# SOCConfiguration.net
KiCad netlist of a schematic drawn in Altium Designer
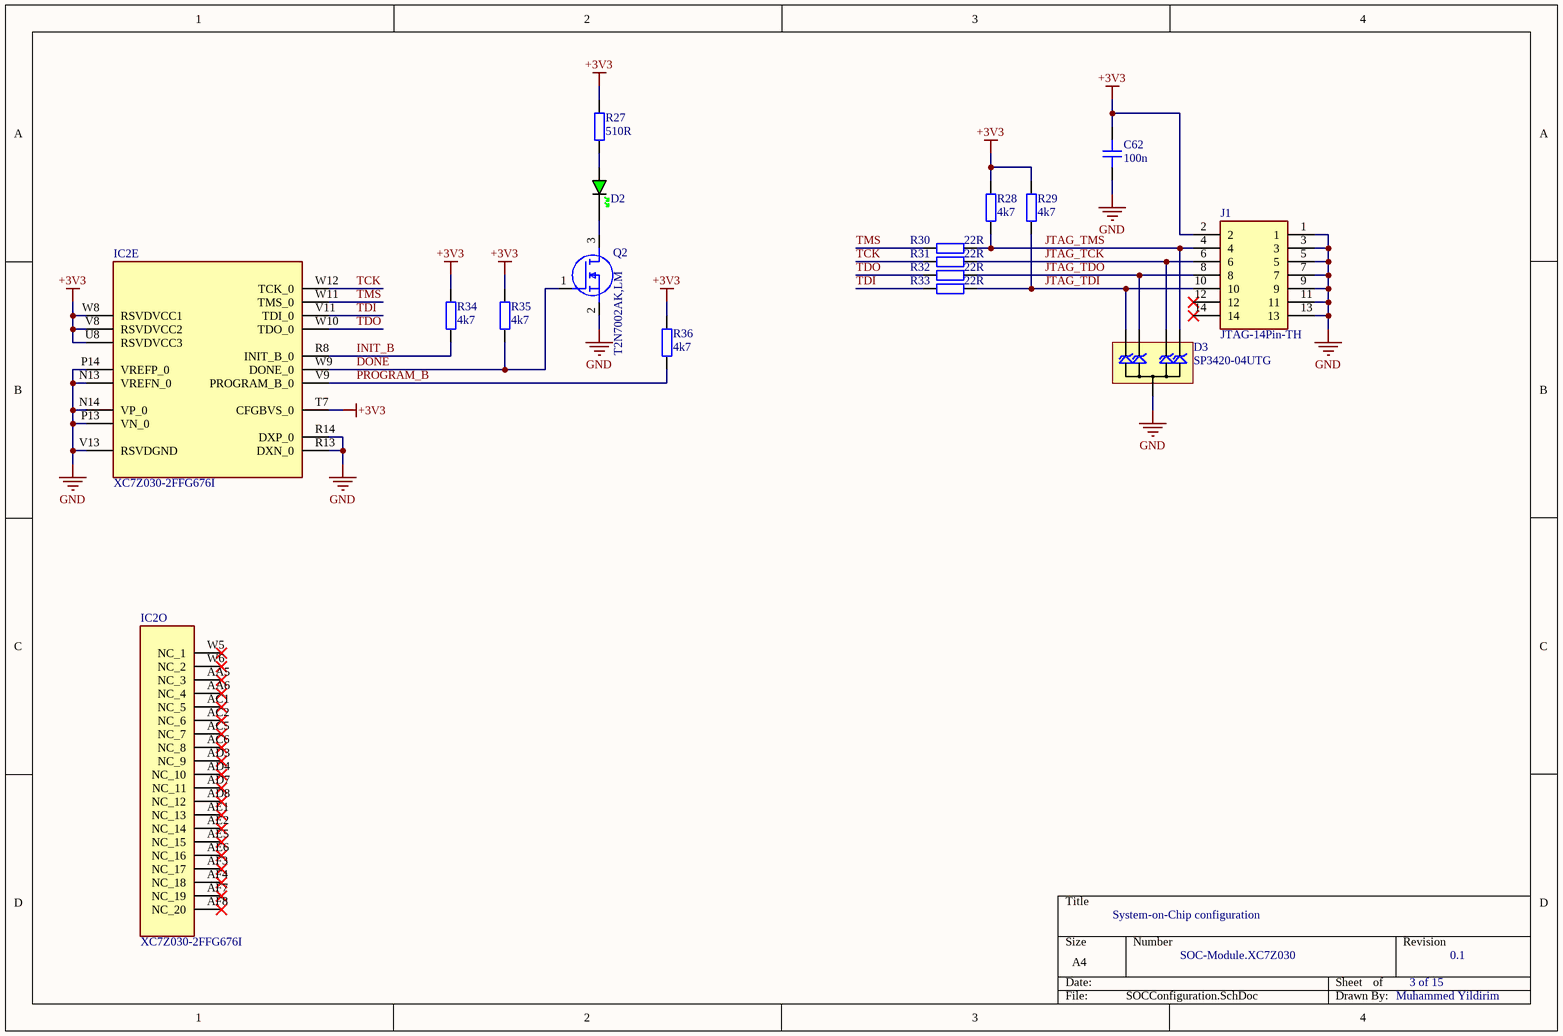
[diagram p0: SOCConfiguration.SchDoc]

(export (version "E")
  (design (tool "Eeschema 10.0.6"))
  (components
    (comp (ref "C62")
      (value "100n")
      (footprint "CAP_0402")
      (description "Capacitor SMD 0402")
      (libsource (lib "Schematic-Lib-PhilsLab") (part "CAP_0402"))
    )
    (comp (ref "D2")
      (value "GREEN")
      (footprint "LED_0603_GREEN")
      (description "LED 0603 GREEN SMD")
      (libsource (lib "Schematic-Lib-PhilsLab") (part "LED_0603_GREEN"))
    )
    (comp (ref "D3")
      (value "SP3420-04UTG")
      (footprint "uDFN-10")
      (description "TVS Diode Array Low Capacitance ESD Protection 4-Channel (Vwork=3V3, Vclamp=6V)")
      (fields (field (name "MANUFACTURER") "Littelfuse"))
      (libsource (lib "Schematic-Lib-PhilsLab") (part "SP3420-04UTG"))
    )
    (comp (ref "IC2")
      (value "XC7Z030-2FFG676I")
      (footprint "XC7Z030PCBLib:BGA676C100P26X26_2700X2700X324")
      (description "Integrated Circuit")
      (fields (field (name "MOUSER PART NUMBER") "217-XC7Z030-2FFG676I"))
      (libsource (lib "XC7Z030SCHLib") (part "XC7Z030-2FFG676I"))
    )
    (comp (ref "J1")
      (value "JTAG-14Pin-TH")
      (footprint "XC7Z030PCBLib:14Pin-TH")
      (description "Connector")
      (fields
        (field (name "MANUFACTURER_PART_NUMBER") "87832-1416")
        (field (name "MOUSER PART NUMBER") "538-87832-1416")
      )
      (libsource (lib "XC7Z030SCHLib") (part "JTAG-14Pin-TH"))
    )
    (comp (ref "Q2")
      (value "T2N7002AK,LM")
      (footprint "Footprint-Lib-PhilsLab:TBAT54CLM")
      (description "MOSFET (N-Channel)")
      (fields (field (name "MOUSER PART NUMBER") "757-T2N7002AKLM"))
      (libsource (lib "Schematic-Lib-PhilsLab") (part "T2N7002AK,LM"))
    )
    (comp (ref "R27")
      (value "510R")
      (footprint "RES_0603")
      (description "Resistor SMD 0603")
      (libsource (lib "Schematic-Lib-PhilsLab") (part "RES_0603"))
    )
    (comp (ref "R28")
      (value "4k7")
      (footprint "RES_0201")
      (description "Resistor SMD 0201")
      (libsource (lib "Schematic-Lib-PhilsLab") (part "RES_0201"))
    )
    (comp (ref "R29")
      (value "4k7")
      (footprint "RES_0201")
      (description "Resistor SMD 0201")
      (libsource (lib "Schematic-Lib-PhilsLab") (part "RES_0201"))
    )
    (comp (ref "R30")
      (value "22R")
      (footprint "RES_0201")
      (description "Resistor SMD 0201")
      (libsource (lib "Schematic-Lib-PhilsLab") (part "RES_0201"))
    )
    (comp (ref "R31")
      (value "22R")
      (footprint "RES_0201")
      (description "Resistor SMD 0201")
      (libsource (lib "Schematic-Lib-PhilsLab") (part "RES_0201"))
    )
    (comp (ref "R32")
      (value "22R")
      (footprint "RES_0201")
      (description "Resistor SMD 0201")
      (libsource (lib "Schematic-Lib-PhilsLab") (part "RES_0201"))
    )
    (comp (ref "R33")
      (value "22R")
      (footprint "RES_0201")
      (description "Resistor SMD 0201")
      (libsource (lib "Schematic-Lib-PhilsLab") (part "RES_0201"))
    )
    (comp (ref "R34")
      (value "4k7")
      (footprint "RES_0201")
      (description "Resistor SMD 0201")
      (libsource (lib "Schematic-Lib-PhilsLab") (part "RES_0201"))
    )
    (comp (ref "R35")
      (value "4k7")
      (footprint "RES_0201")
      (description "Resistor SMD 0201")
      (libsource (lib "Schematic-Lib-PhilsLab") (part "RES_0201"))
    )
    (comp (ref "R36")
      (value "4k7")
      (footprint "RES_0201")
      (description "Resistor SMD 0201")
      (libsource (lib "Schematic-Lib-PhilsLab") (part "RES_0201"))
    )
  )
  (nets
    (net (code "1") (name "+3V3") (class "Default")
      (node (ref "C62") (pin "2") (pinfunction "2_2") (pintype "passive"))
      (node (ref "IC2") (pin "T7") (pinfunction "CFGBVS_0_T7") (pintype "passive"))
      (node (ref "IC2") (pin "U8") (pinfunction "RSVDVCC3_U8") (pintype "passive"))
      (node (ref "IC2") (pin "V8") (pinfunction "RSVDVCC2_V8") (pintype "passive"))
      (node (ref "IC2") (pin "W8") (pinfunction "RSVDVCC1_W8") (pintype "passive"))
      (node (ref "J1") (pin "2") (pinfunction "2_2") (pintype "passive"))
      (node (ref "R27") (pin "2") (pinfunction "2_2") (pintype "passive"))
      (node (ref "R28") (pin "2") (pinfunction "2_2") (pintype "passive"))
      (node (ref "R29") (pin "2") (pinfunction "2_2") (pintype "passive"))
      (node (ref "R34") (pin "2") (pinfunction "2_2") (pintype "passive"))
      (node (ref "R35") (pin "2") (pinfunction "2_2") (pintype "passive"))
      (node (ref "R36") (pin "2") (pinfunction "2_2") (pintype "passive"))
    )
    (net (code "2") (name "/DONE") (class "Default")
      (node (ref "IC2") (pin "W9") (pinfunction "DONE_0_W9") (pintype "passive"))
      (node (ref "Q2") (pin "1") (pinfunction "G_1") (pintype "passive"))
      (node (ref "R35") (pin "1") (pinfunction "1_1") (pintype "passive"))
    )
    (net (code "3") (name "/INIT_B") (class "Default")
      (node (ref "IC2") (pin "R8") (pinfunction "INIT_B_0_R8") (pintype "passive"))
      (node (ref "R34") (pin "1") (pinfunction "1_1") (pintype "passive"))
    )
    (net (code "4") (name "/JTAG_TCK") (class "Default")
      (node (ref "D3") (pin "47") (pintype "passive"))
      (node (ref "J1") (pin "6") (pinfunction "6_6") (pintype "passive"))
      (node (ref "R31") (pin "1") (pinfunction "1_1") (pintype "passive"))
    )
    (net (code "5") (name "/JTAG_TDI") (class "Default")
      (node (ref "D3") (pin "110") (pintype "passive"))
      (node (ref "J1") (pin "10") (pinfunction "10_10") (pintype "passive"))
      (node (ref "R29") (pin "1") (pinfunction "1_1") (pintype "passive"))
      (node (ref "R33") (pin "1") (pinfunction "1_1") (pintype "passive"))
    )
    (net (code "6") (name "/JTAG_TDO") (class "Default")
      (node (ref "D3") (pin "29") (pintype "passive"))
      (node (ref "J1") (pin "8") (pinfunction "8_8") (pintype "passive"))
      (node (ref "R32") (pin "1") (pinfunction "1_1") (pintype "passive"))
    )
    (net (code "7") (name "/JTAG_TMS") (class "Default")
      (node (ref "D3") (pin "56") (pintype "passive"))
      (node (ref "J1") (pin "4") (pinfunction "4_4") (pintype "passive"))
      (node (ref "R28") (pin "1") (pinfunction "1_1") (pintype "passive"))
      (node (ref "R30") (pin "1") (pinfunction "1_1") (pintype "passive"))
    )
    (net (code "8") (name "/PROGRAM_B") (class "Default")
      (node (ref "IC2") (pin "V9") (pinfunction "PROGRAM_B_0_V9") (pintype "passive"))
      (node (ref "R36") (pin "1") (pinfunction "1_1") (pintype "passive"))
    )
    (net (code "9") (name "/TCK") (class "Default")
      (node (ref "IC2") (pin "W12") (pinfunction "TCK_0_W12") (pintype "passive"))
      (node (ref "R31") (pin "2") (pinfunction "2_2") (pintype "passive"))
    )
    (net (code "10") (name "/TDI") (class "Default")
      (node (ref "IC2") (pin "V11") (pinfunction "TDI_0_V11") (pintype "passive"))
      (node (ref "R33") (pin "2") (pinfunction "2_2") (pintype "passive"))
    )
    (net (code "11") (name "/TDO") (class "Default")
      (node (ref "IC2") (pin "W10") (pinfunction "TDO_0_W10") (pintype "passive"))
      (node (ref "R32") (pin "2") (pinfunction "2_2") (pintype "passive"))
    )
    (net (code "12") (name "/TMS") (class "Default")
      (node (ref "IC2") (pin "W11") (pinfunction "TMS_0_W11") (pintype "passive"))
      (node (ref "R30") (pin "2") (pinfunction "2_2") (pintype "passive"))
    )
    (net (code "13") (name "GND") (class "Default")
      (node (ref "C62") (pin "1") (pinfunction "1_1") (pintype "passive"))
      (node (ref "D3") (pin "38") (pinfunction "GND_38") (pintype "passive"))
      (node (ref "IC2") (pin "N13") (pinfunction "VREFN_0_N13") (pintype "passive"))
      (node (ref "IC2") (pin "N14") (pinfunction "VP_0_N14") (pintype "passive"))
      (node (ref "IC2") (pin "P13") (pinfunction "VN_0_P13") (pintype "passive"))
      (node (ref "IC2") (pin "P14") (pinfunction "VREFP_0_P14") (pintype "passive"))
      (node (ref "IC2") (pin "R13") (pinfunction "DXN_0_R13") (pintype "passive"))
      (node (ref "IC2") (pin "R14") (pinfunction "DXP_0_R14") (pintype "passive"))
      (node (ref "IC2") (pin "V13") (pinfunction "RSVDGND_V13") (pintype "passive"))
      (node (ref "J1") (pin "1") (pinfunction "1_1") (pintype "passive"))
      (node (ref "J1") (pin "11") (pinfunction "11_11") (pintype "passive"))
      (node (ref "J1") (pin "13") (pinfunction "13_13") (pintype "passive"))
      (node (ref "J1") (pin "3") (pinfunction "3_3") (pintype "passive"))
      (node (ref "J1") (pin "5") (pinfunction "5_5") (pintype "passive"))
      (node (ref "J1") (pin "7") (pinfunction "7_7") (pintype "passive"))
      (node (ref "J1") (pin "9") (pinfunction "9_9") (pintype "passive"))
      (node (ref "Q2") (pin "2") (pinfunction "S_2") (pintype "passive"))
    )
    (net (code "14") (name "Net-(D2-PadA)") (class "Default")
      (node (ref "D2") (pin "A") (pinfunction "A_A") (pintype "passive"))
      (node (ref "R27") (pin "1") (pinfunction "1_1") (pintype "passive"))
    )
    (net (code "15") (name "Net-(Q2-D)") (class "Default")
      (node (ref "D2") (pin "K") (pinfunction "K_K") (pintype "passive"))
      (node (ref "Q2") (pin "3") (pinfunction "D_3") (pintype "passive"))
    )
    (net (code "16") (name "unconnected-(IC2O-NC_1-PadW5)") (class "Default")
      (node (ref "IC2") (pin "W5") (pinfunction "NC_1_W5") (pintype "passive+no_connect"))
    )
    (net (code "17") (name "unconnected-(IC2O-NC_2-PadW6)") (class "Default")
      (node (ref "IC2") (pin "W6") (pinfunction "NC_2_W6") (pintype "passive+no_connect"))
    )
    (net (code "18") (name "unconnected-(IC2O-NC_3-PadAA5)") (class "Default")
      (node (ref "IC2") (pin "AA5") (pinfunction "NC_3_AA5") (pintype "passive+no_connect"))
    )
    (net (code "19") (name "unconnected-(IC2O-NC_4-PadAA6)") (class "Default")
      (node (ref "IC2") (pin "AA6") (pinfunction "NC_4_AA6") (pintype "passive+no_connect"))
    )
    (net (code "20") (name "unconnected-(IC2O-NC_5-PadAC1)") (class "Default")
      (node (ref "IC2") (pin "AC1") (pinfunction "NC_5_AC1") (pintype "passive+no_connect"))
    )
    (net (code "21") (name "unconnected-(IC2O-NC_6-PadAC2)") (class "Default")
      (node (ref "IC2") (pin "AC2") (pinfunction "NC_6_AC2") (pintype "passive+no_connect"))
    )
    (net (code "22") (name "unconnected-(IC2O-NC_7-PadAC5)") (class "Default")
      (node (ref "IC2") (pin "AC5") (pinfunction "NC_7_AC5") (pintype "passive+no_connect"))
    )
    (net (code "23") (name "unconnected-(IC2O-NC_8-PadAC6)") (class "Default")
      (node (ref "IC2") (pin "AC6") (pinfunction "NC_8_AC6") (pintype "passive+no_connect"))
    )
    (net (code "24") (name "unconnected-(IC2O-NC_9-PadAD3)") (class "Default")
      (node (ref "IC2") (pin "AD3") (pinfunction "NC_9_AD3") (pintype "passive+no_connect"))
    )
    (net (code "25") (name "unconnected-(IC2O-NC_10-PadAD4)") (class "Default")
      (node (ref "IC2") (pin "AD4") (pinfunction "NC_10_AD4") (pintype "passive+no_connect"))
    )
    (net (code "26") (name "unconnected-(IC2O-NC_11-PadAD7)") (class "Default")
      (node (ref "IC2") (pin "AD7") (pinfunction "NC_11_AD7") (pintype "passive+no_connect"))
    )
    (net (code "27") (name "unconnected-(IC2O-NC_12-PadAD8)") (class "Default")
      (node (ref "IC2") (pin "AD8") (pinfunction "NC_12_AD8") (pintype "passive+no_connect"))
    )
    (net (code "28") (name "unconnected-(IC2O-NC_13-PadAE1)") (class "Default")
      (node (ref "IC2") (pin "AE1") (pinfunction "NC_13_AE1") (pintype "passive+no_connect"))
    )
    (net (code "29") (name "unconnected-(IC2O-NC_14-PadAE2)") (class "Default")
      (node (ref "IC2") (pin "AE2") (pinfunction "NC_14_AE2") (pintype "passive+no_connect"))
    )
    (net (code "30") (name "unconnected-(IC2O-NC_15-PadAE5)") (class "Default")
      (node (ref "IC2") (pin "AE5") (pinfunction "NC_15_AE5") (pintype "passive+no_connect"))
    )
    (net (code "31") (name "unconnected-(IC2O-NC_16-PadAE6)") (class "Default")
      (node (ref "IC2") (pin "AE6") (pinfunction "NC_16_AE6") (pintype "passive+no_connect"))
    )
    (net (code "32") (name "unconnected-(IC2O-NC_17-PadAF3)") (class "Default")
      (node (ref "IC2") (pin "AF3") (pinfunction "NC_17_AF3") (pintype "passive+no_connect"))
    )
    (net (code "33") (name "unconnected-(IC2O-NC_18-PadAF4)") (class "Default")
      (node (ref "IC2") (pin "AF4") (pinfunction "NC_18_AF4") (pintype "passive+no_connect"))
    )
    (net (code "34") (name "unconnected-(IC2O-NC_19-PadAF7)") (class "Default")
      (node (ref "IC2") (pin "AF7") (pinfunction "NC_19_AF7") (pintype "passive+no_connect"))
    )
    (net (code "35") (name "unconnected-(IC2O-NC_20-PadAF8)") (class "Default")
      (node (ref "IC2") (pin "AF8") (pinfunction "NC_20_AF8") (pintype "passive+no_connect"))
    )
    (net (code "36") (name "unconnected-(J1-Pad12)") (class "Default")
      (node (ref "J1") (pin "12") (pinfunction "12_12") (pintype "passive+no_connect"))
    )
    (net (code "37") (name "unconnected-(J1-Pad14)") (class "Default")
      (node (ref "J1") (pin "14") (pinfunction "14_14") (pintype "passive+no_connect"))
    )
  )
)
